# untitled2.net
KiCad netlist of a schematic drawn in EAGLE
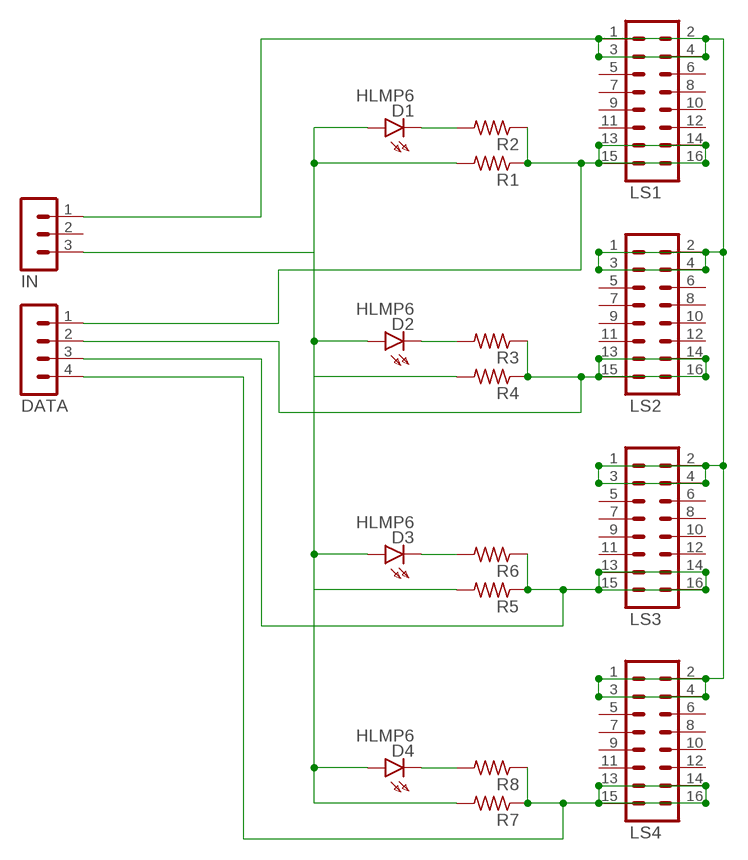
[diagram p0: schematic, sheet 1]

(export (version "E")
  (design (tool "Eeschema 10.0.6"))
  (components
    (comp (ref "D1")
      (value "HLMP6")
      (footprint "eagle-import:HLMP6")
      (fields (field (name "MF") "AGILENT TECHNOLOGIES") (field (name "MPN") "HLMP-6500"))
      (libsource (lib "eagle-import") (part "HLMP6"))
    )
    (comp (ref "D2")
      (value "HLMP6")
      (footprint "eagle-import:HLMP6")
      (fields (field (name "MF") "AGILENT TECHNOLOGIES") (field (name "MPN") "HLMP-6500"))
      (libsource (lib "eagle-import") (part "HLMP6"))
    )
    (comp (ref "D3")
      (value "HLMP6")
      (footprint "eagle-import:HLMP6")
      (fields (field (name "MF") "AGILENT TECHNOLOGIES") (field (name "MPN") "HLMP-6500"))
      (libsource (lib "eagle-import") (part "HLMP6"))
    )
    (comp (ref "D4")
      (value "HLMP6")
      (footprint "eagle-import:HLMP6")
      (fields (field (name "MF") "AGILENT TECHNOLOGIES") (field (name "MPN") "HLMP-6500"))
      (libsource (lib "eagle-import") (part "HLMP6"))
    )
    (comp (ref "DATA")
      (value "MA04-1")
      (footprint "eagle-import:MA04-1")
      (libsource (lib "eagle-import") (part "MA04-1"))
    )
    (comp (ref "IN")
      (value "MA03-1")
      (footprint "eagle-import:MA03-1")
      (libsource (lib "eagle-import") (part "MA03-1"))
    )
    (comp (ref "LS1")
      (value "MA08-2")
      (footprint "eagle-import:MA08-2")
      (libsource (lib "eagle-import") (part "MA08-2"))
    )
    (comp (ref "LS2")
      (value "MA08-2")
      (footprint "eagle-import:MA08-2")
      (libsource (lib "eagle-import") (part "MA08-2"))
    )
    (comp (ref "LS3")
      (value "MA08-2")
      (footprint "eagle-import:MA08-2")
      (libsource (lib "eagle-import") (part "MA08-2"))
    )
    (comp (ref "LS4")
      (value "MA08-2")
      (footprint "eagle-import:MA08-2")
      (libsource (lib "eagle-import") (part "MA08-2"))
    )
    (comp (ref "R1")
      (value "R-US_0207/10")
      (footprint "eagle-import:0207_10")
      (libsource (lib "eagle-import") (part "R-US_0207/10"))
    )
    (comp (ref "R2")
      (value "R-US_0207/10")
      (footprint "eagle-import:0207_10")
      (libsource (lib "eagle-import") (part "R-US_0207/10"))
    )
    (comp (ref "R3")
      (value "R-US_0207/10")
      (footprint "eagle-import:0207_10")
      (libsource (lib "eagle-import") (part "R-US_0207/10"))
    )
    (comp (ref "R4")
      (value "R-US_0207/10")
      (footprint "eagle-import:0207_10")
      (libsource (lib "eagle-import") (part "R-US_0207/10"))
    )
    (comp (ref "R5")
      (value "R-US_0207/10")
      (footprint "eagle-import:0207_10")
      (libsource (lib "eagle-import") (part "R-US_0207/10"))
    )
    (comp (ref "R6")
      (value "R-US_0207/10")
      (footprint "eagle-import:0207_10")
      (libsource (lib "eagle-import") (part "R-US_0207/10"))
    )
    (comp (ref "R7")
      (value "R-US_0207/10")
      (footprint "eagle-import:0207_10")
      (libsource (lib "eagle-import") (part "R-US_0207/10"))
    )
    (comp (ref "R8")
      (value "R-US_0207/10")
      (footprint "eagle-import:0207_10")
      (libsource (lib "eagle-import") (part "R-US_0207/10"))
    )
  )
  (nets
    (net (code "1") (name "Net-(D1-PadA)") (class "Default")
      (node (ref "D1") (pin "A") (pinfunction "A_A") (pintype "passive"))
      (node (ref "D2") (pin "A") (pinfunction "A_A") (pintype "passive"))
      (node (ref "D3") (pin "A") (pinfunction "A_A") (pintype "passive"))
      (node (ref "D4") (pin "A") (pinfunction "A_A") (pintype "passive"))
      (node (ref "IN") (pin "3") (pinfunction "3_3") (pintype "passive"))
      (node (ref "R1") (pin "2") (pinfunction "2_2") (pintype "passive"))
      (node (ref "R4") (pin "2") (pinfunction "2_2") (pintype "passive"))
      (node (ref "R5") (pin "2") (pinfunction "2_2") (pintype "passive"))
      (node (ref "R7") (pin "2") (pinfunction "2_2") (pintype "passive"))
    )
    (net (code "2") (name "Net-(D1-PadK)") (class "Default")
      (node (ref "D1") (pin "K") (pinfunction "K_K") (pintype "passive"))
      (node (ref "R2") (pin "2") (pinfunction "2_2") (pintype "passive"))
    )
    (net (code "3") (name "Net-(D2-PadK)") (class "Default")
      (node (ref "D2") (pin "K") (pinfunction "K_K") (pintype "passive"))
      (node (ref "R3") (pin "2") (pinfunction "2_2") (pintype "passive"))
    )
    (net (code "4") (name "Net-(D3-PadK)") (class "Default")
      (node (ref "D3") (pin "K") (pinfunction "K_K") (pintype "passive"))
      (node (ref "R6") (pin "2") (pinfunction "2_2") (pintype "passive"))
    )
    (net (code "5") (name "Net-(D4-PadK)") (class "Default")
      (node (ref "D4") (pin "K") (pinfunction "K_K") (pintype "passive"))
      (node (ref "R8") (pin "2") (pinfunction "2_2") (pintype "passive"))
    )
    (net (code "6") (name "Net-(DATA-Pad1)") (class "Default")
      (node (ref "DATA") (pin "1") (pinfunction "1_1") (pintype "passive"))
      (node (ref "LS1") (pin "13") (pinfunction "13_13") (pintype "passive"))
      (node (ref "LS1") (pin "14") (pinfunction "14_14") (pintype "passive"))
      (node (ref "LS1") (pin "15") (pinfunction "15_15") (pintype "passive"))
      (node (ref "LS1") (pin "16") (pinfunction "16_16") (pintype "passive"))
      (node (ref "R1") (pin "1") (pinfunction "1_1") (pintype "passive"))
      (node (ref "R2") (pin "1") (pinfunction "1_1") (pintype "passive"))
    )
    (net (code "7") (name "Net-(DATA-Pad2)") (class "Default")
      (node (ref "DATA") (pin "2") (pinfunction "2_2") (pintype "passive"))
      (node (ref "LS2") (pin "13") (pinfunction "13_13") (pintype "passive"))
      (node (ref "LS2") (pin "14") (pinfunction "14_14") (pintype "passive"))
      (node (ref "LS2") (pin "15") (pinfunction "15_15") (pintype "passive"))
      (node (ref "LS2") (pin "16") (pinfunction "16_16") (pintype "passive"))
      (node (ref "R3") (pin "1") (pinfunction "1_1") (pintype "passive"))
      (node (ref "R4") (pin "1") (pinfunction "1_1") (pintype "passive"))
    )
    (net (code "8") (name "Net-(DATA-Pad3)") (class "Default")
      (node (ref "DATA") (pin "3") (pinfunction "3_3") (pintype "passive"))
      (node (ref "LS3") (pin "13") (pinfunction "13_13") (pintype "passive"))
      (node (ref "LS3") (pin "14") (pinfunction "14_14") (pintype "passive"))
      (node (ref "LS3") (pin "15") (pinfunction "15_15") (pintype "passive"))
      (node (ref "LS3") (pin "16") (pinfunction "16_16") (pintype "passive"))
      (node (ref "R5") (pin "1") (pinfunction "1_1") (pintype "passive"))
      (node (ref "R6") (pin "1") (pinfunction "1_1") (pintype "passive"))
    )
    (net (code "9") (name "Net-(DATA-Pad4)") (class "Default")
      (node (ref "DATA") (pin "4") (pinfunction "4_4") (pintype "passive"))
      (node (ref "LS4") (pin "13") (pinfunction "13_13") (pintype "passive"))
      (node (ref "LS4") (pin "14") (pinfunction "14_14") (pintype "passive"))
      (node (ref "LS4") (pin "15") (pinfunction "15_15") (pintype "passive"))
      (node (ref "LS4") (pin "16") (pinfunction "16_16") (pintype "passive"))
      (node (ref "R7") (pin "1") (pinfunction "1_1") (pintype "passive"))
      (node (ref "R8") (pin "1") (pinfunction "1_1") (pintype "passive"))
    )
    (net (code "10") (name "Net-(IN-Pad1)") (class "Default")
      (node (ref "IN") (pin "1") (pinfunction "1_1") (pintype "passive"))
      (node (ref "LS1") (pin "1") (pinfunction "1_1") (pintype "passive"))
      (node (ref "LS1") (pin "2") (pinfunction "2_2") (pintype "passive"))
      (node (ref "LS1") (pin "3") (pinfunction "3_3") (pintype "passive"))
      (node (ref "LS1") (pin "4") (pinfunction "4_4") (pintype "passive"))
      (node (ref "LS2") (pin "1") (pinfunction "1_1") (pintype "passive"))
      (node (ref "LS2") (pin "2") (pinfunction "2_2") (pintype "passive"))
      (node (ref "LS2") (pin "3") (pinfunction "3_3") (pintype "passive"))
      (node (ref "LS2") (pin "4") (pinfunction "4_4") (pintype "passive"))
      (node (ref "LS3") (pin "1") (pinfunction "1_1") (pintype "passive"))
      (node (ref "LS3") (pin "2") (pinfunction "2_2") (pintype "passive"))
      (node (ref "LS3") (pin "3") (pinfunction "3_3") (pintype "passive"))
      (node (ref "LS3") (pin "4") (pinfunction "4_4") (pintype "passive"))
      (node (ref "LS4") (pin "1") (pinfunction "1_1") (pintype "passive"))
      (node (ref "LS4") (pin "2") (pinfunction "2_2") (pintype "passive"))
      (node (ref "LS4") (pin "3") (pinfunction "3_3") (pintype "passive"))
      (node (ref "LS4") (pin "4") (pinfunction "4_4") (pintype "passive"))
    )
    (net (code "11") (name "unconnected-(IN-Pad2)") (class "Default")
      (node (ref "IN") (pin "2") (pinfunction "2_2") (pintype "passive"))
    )
    (net (code "12") (name "unconnected-(LS1-Pad5)") (class "Default")
      (node (ref "LS1") (pin "5") (pinfunction "5_5") (pintype "passive"))
    )
    (net (code "13") (name "unconnected-(LS1-Pad6)") (class "Default")
      (node (ref "LS1") (pin "6") (pinfunction "6_6") (pintype "passive"))
    )
    (net (code "14") (name "unconnected-(LS1-Pad7)") (class "Default")
      (node (ref "LS1") (pin "7") (pinfunction "7_7") (pintype "passive"))
    )
    (net (code "15") (name "unconnected-(LS1-Pad8)") (class "Default")
      (node (ref "LS1") (pin "8") (pinfunction "8_8") (pintype "passive"))
    )
    (net (code "16") (name "unconnected-(LS1-Pad9)") (class "Default")
      (node (ref "LS1") (pin "9") (pinfunction "9_9") (pintype "passive"))
    )
    (net (code "17") (name "unconnected-(LS1-Pad10)") (class "Default")
      (node (ref "LS1") (pin "10") (pinfunction "10_10") (pintype "passive"))
    )
    (net (code "18") (name "unconnected-(LS1-Pad11)") (class "Default")
      (node (ref "LS1") (pin "11") (pinfunction "11_11") (pintype "passive"))
    )
    (net (code "19") (name "unconnected-(LS1-Pad12)") (class "Default")
      (node (ref "LS1") (pin "12") (pinfunction "12_12") (pintype "passive"))
    )
    (net (code "20") (name "unconnected-(LS2-Pad5)") (class "Default")
      (node (ref "LS2") (pin "5") (pinfunction "5_5") (pintype "passive"))
    )
    (net (code "21") (name "unconnected-(LS2-Pad6)") (class "Default")
      (node (ref "LS2") (pin "6") (pinfunction "6_6") (pintype "passive"))
    )
    (net (code "22") (name "unconnected-(LS2-Pad7)") (class "Default")
      (node (ref "LS2") (pin "7") (pinfunction "7_7") (pintype "passive"))
    )
    (net (code "23") (name "unconnected-(LS2-Pad8)") (class "Default")
      (node (ref "LS2") (pin "8") (pinfunction "8_8") (pintype "passive"))
    )
    (net (code "24") (name "unconnected-(LS2-Pad9)") (class "Default")
      (node (ref "LS2") (pin "9") (pinfunction "9_9") (pintype "passive"))
    )
    (net (code "25") (name "unconnected-(LS2-Pad10)") (class "Default")
      (node (ref "LS2") (pin "10") (pinfunction "10_10") (pintype "passive"))
    )
    (net (code "26") (name "unconnected-(LS2-Pad11)") (class "Default")
      (node (ref "LS2") (pin "11") (pinfunction "11_11") (pintype "passive"))
    )
    (net (code "27") (name "unconnected-(LS2-Pad12)") (class "Default")
      (node (ref "LS2") (pin "12") (pinfunction "12_12") (pintype "passive"))
    )
    (net (code "28") (name "unconnected-(LS3-Pad5)") (class "Default")
      (node (ref "LS3") (pin "5") (pinfunction "5_5") (pintype "passive"))
    )
    (net (code "29") (name "unconnected-(LS3-Pad6)") (class "Default")
      (node (ref "LS3") (pin "6") (pinfunction "6_6") (pintype "passive"))
    )
    (net (code "30") (name "unconnected-(LS3-Pad7)") (class "Default")
      (node (ref "LS3") (pin "7") (pinfunction "7_7") (pintype "passive"))
    )
    (net (code "31") (name "unconnected-(LS3-Pad8)") (class "Default")
      (node (ref "LS3") (pin "8") (pinfunction "8_8") (pintype "passive"))
    )
    (net (code "32") (name "unconnected-(LS3-Pad9)") (class "Default")
      (node (ref "LS3") (pin "9") (pinfunction "9_9") (pintype "passive"))
    )
    (net (code "33") (name "unconnected-(LS3-Pad10)") (class "Default")
      (node (ref "LS3") (pin "10") (pinfunction "10_10") (pintype "passive"))
    )
    (net (code "34") (name "unconnected-(LS3-Pad11)") (class "Default")
      (node (ref "LS3") (pin "11") (pinfunction "11_11") (pintype "passive"))
    )
    (net (code "35") (name "unconnected-(LS3-Pad12)") (class "Default")
      (node (ref "LS3") (pin "12") (pinfunction "12_12") (pintype "passive"))
    )
    (net (code "36") (name "unconnected-(LS4-Pad5)") (class "Default")
      (node (ref "LS4") (pin "5") (pinfunction "5_5") (pintype "passive"))
    )
    (net (code "37") (name "unconnected-(LS4-Pad6)") (class "Default")
      (node (ref "LS4") (pin "6") (pinfunction "6_6") (pintype "passive"))
    )
    (net (code "38") (name "unconnected-(LS4-Pad7)") (class "Default")
      (node (ref "LS4") (pin "7") (pinfunction "7_7") (pintype "passive"))
    )
    (net (code "39") (name "unconnected-(LS4-Pad8)") (class "Default")
      (node (ref "LS4") (pin "8") (pinfunction "8_8") (pintype "passive"))
    )
    (net (code "40") (name "unconnected-(LS4-Pad9)") (class "Default")
      (node (ref "LS4") (pin "9") (pinfunction "9_9") (pintype "passive"))
    )
    (net (code "41") (name "unconnected-(LS4-Pad10)") (class "Default")
      (node (ref "LS4") (pin "10") (pinfunction "10_10") (pintype "passive"))
    )
    (net (code "42") (name "unconnected-(LS4-Pad11)") (class "Default")
      (node (ref "LS4") (pin "11") (pinfunction "11_11") (pintype "passive"))
    )
    (net (code "43") (name "unconnected-(LS4-Pad12)") (class "Default")
      (node (ref "LS4") (pin "12") (pinfunction "12_12") (pintype "passive"))
    )
  )
)
